# Other.net
KiCad netlist of a schematic drawn in Altium Designer
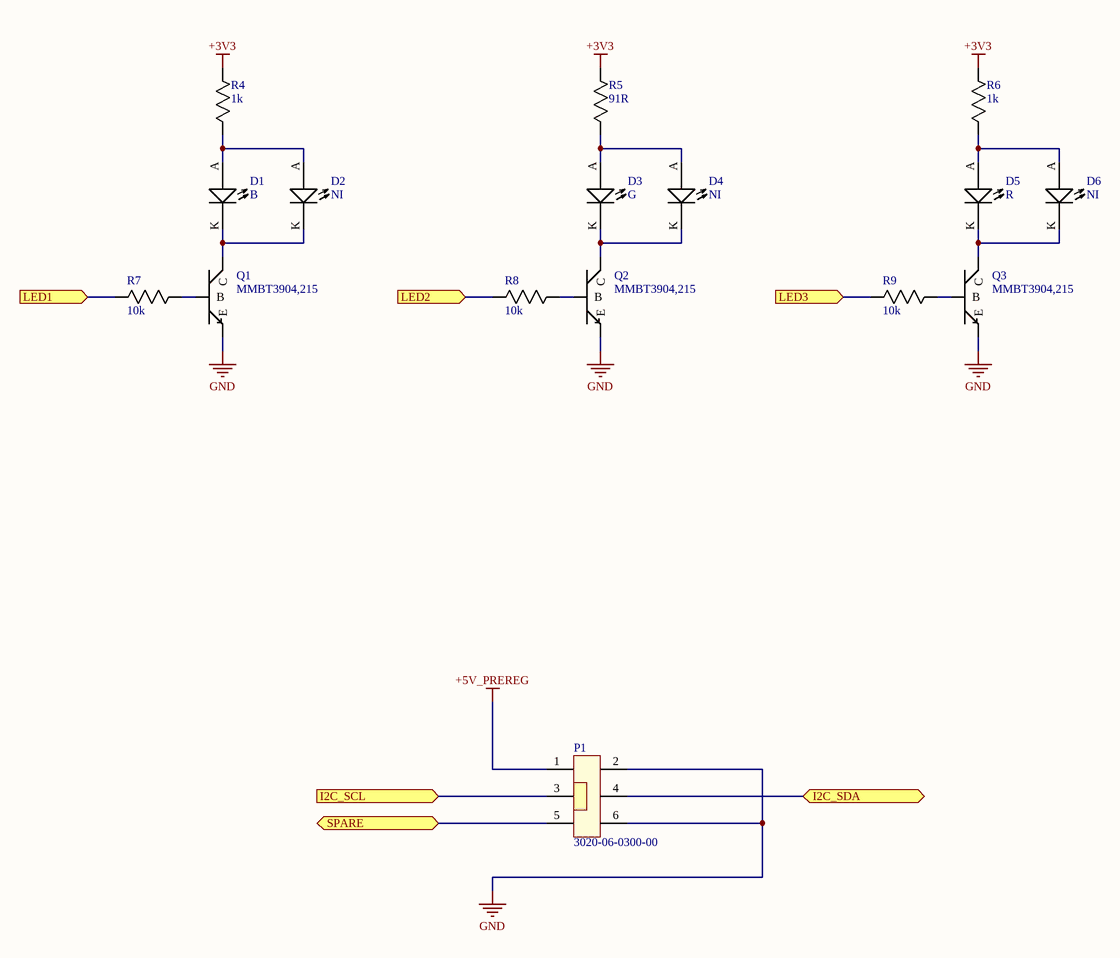
[diagram p0: Other.SchDoc]

(export (version "E")
  (design (tool "Eeschema 10.0.6"))
  (components
    (comp (ref "D1")
      (value "Diode_LED")
      (footprint "0805_LED")
      (description "LED")
      (fields (field (name "MFG") "Wurth") (field (name "TYPE") "B"))
      (libsource (lib "ADAPTONE_CARTE_DE_SON") (part "Diode_LED"))
    )
    (comp (ref "D2")
      (value "Diode_LED")
      (footprint "0805_LED")
      (description "LED")
      (fields (field (name "NI") "NI"))
      (libsource (lib "ADAPTONE_CARTE_DE_SON") (part "Diode_LED"))
    )
    (comp (ref "D3")
      (value "Diode_LED")
      (footprint "0805_LED")
      (description "LED")
      (fields (field (name "MFG") "Osram") (field (name "TYPE") "G"))
      (libsource (lib "ADAPTONE_CARTE_DE_SON") (part "Diode_LED"))
    )
    (comp (ref "D4")
      (value "Diode_LED")
      (footprint "0805_LED")
      (description "LED")
      (fields (field (name "NI") "NI"))
      (libsource (lib "ADAPTONE_CARTE_DE_SON") (part "Diode_LED"))
    )
    (comp (ref "D5")
      (value "Diode_LED")
      (footprint "0805_LED")
      (description "LED")
      (fields (field (name "MFG") "Osram") (field (name "TYPE") "R"))
      (libsource (lib "ADAPTONE_CARTE_DE_SON") (part "Diode_LED"))
    )
    (comp (ref "D6")
      (value "Diode_LED")
      (footprint "0805_LED")
      (description "LED")
      (fields (field (name "NI") "NI"))
      (libsource (lib "ADAPTONE_CARTE_DE_SON") (part "Diode_LED"))
    )
    (comp (ref "P1")
      (value "CON6_3020-06-0300-00")
      (footprint "CONN6_100mils_pol_SMD")
      (description "6-pins")
      (fields (field (name "MFG") "Harwin") (field (name "MFG_PN") "3020-06-0300-00"))
      (libsource (lib "ADAPTONE_CARTE_DE_SON") (part "CON6_3020-06-0300-00"))
    )
    (comp (ref "Q1")
      (value "BJT_N_GDS")
      (footprint "SOT23_GDS")
      (description "BJT NPN")
      (fields (field (name "MFG") "NXP") (field (name "MFG_PN") "MMBT3904,215"))
      (libsource (lib "ADAPTONE_CARTE_DE_SON") (part "BJT_N_GDS"))
    )
    (comp (ref "Q2")
      (value "BJT_N_GDS")
      (footprint "SOT23_GDS")
      (description "BJT NPN")
      (fields (field (name "MFG") "NXP") (field (name "MFG_PN") "MMBT3904,215"))
      (libsource (lib "ADAPTONE_CARTE_DE_SON") (part "BJT_N_GDS"))
    )
    (comp (ref "Q3")
      (value "BJT_N_GDS")
      (footprint "SOT23_GDS")
      (description "BJT NPN")
      (fields (field (name "MFG") "NXP") (field (name "MFG_PN") "MMBT3904,215"))
      (libsource (lib "ADAPTONE_CARTE_DE_SON") (part "BJT_N_GDS"))
    )
    (comp (ref "R4")
      (value "1k")
      (footprint "0603")
      (description "Resistor")
      (fields (field (name "MFG") "Yageo"))
      (libsource (lib "ADAPTONE_CARTE_DE_SON") (part "Resistor"))
    )
    (comp (ref "R5")
      (value "91R")
      (footprint "0603")
      (description "Resistor")
      (fields (field (name "MFG") "Yageo"))
      (libsource (lib "ADAPTONE_CARTE_DE_SON") (part "Resistor"))
    )
    (comp (ref "R6")
      (value "1k")
      (footprint "0603")
      (description "Resistor")
      (fields (field (name "MFG") "Yageo"))
      (libsource (lib "ADAPTONE_CARTE_DE_SON") (part "Resistor"))
    )
    (comp (ref "R7")
      (value "10k")
      (footprint "0603")
      (description "Resistor")
      (fields (field (name "MFG") "Yageo"))
      (libsource (lib "ADAPTONE_CARTE_DE_SON") (part "Resistor"))
    )
    (comp (ref "R8")
      (value "10k")
      (footprint "0603")
      (description "Resistor")
      (fields (field (name "MFG") "Yageo"))
      (libsource (lib "ADAPTONE_CARTE_DE_SON") (part "Resistor"))
    )
    (comp (ref "R9")
      (value "10k")
      (footprint "0603")
      (description "Resistor")
      (fields (field (name "MFG") "Yageo"))
      (libsource (lib "ADAPTONE_CARTE_DE_SON") (part "Resistor"))
    )
  )
  (nets
    (net (code "1") (name "+3V3") (class "Default")
      (node (ref "R4") (pin "2") (pintype "passive"))
      (node (ref "R5") (pin "2") (pintype "passive"))
      (node (ref "R6") (pin "2") (pintype "passive"))
    )
    (net (code "2") (name "+5V_PREREG") (class "Default") (node (ref "P1") (pin "1") (pintype "passive")))
    (net (code "3") (name "/I2C_SCL") (class "Default") (node (ref "P1") (pin "3") (pintype "passive")))
    (net (code "4") (name "/I2C_SDA") (class "Default") (node (ref "P1") (pin "4") (pintype "passive")))
    (net (code "5") (name "/LED1") (class "Default") (node (ref "R7") (pin "1") (pintype "passive")))
    (net (code "6") (name "/LED2") (class "Default") (node (ref "R8") (pin "1") (pintype "passive")))
    (net (code "7") (name "/LED3") (class "Default") (node (ref "R9") (pin "1") (pintype "passive")))
    (net (code "8") (name "/SPARE") (class "Default") (node (ref "P1") (pin "5") (pintype "passive")))
    (net (code "9") (name "GND") (class "Default")
      (node (ref "P1") (pin "2") (pintype "passive"))
      (node (ref "P1") (pin "6") (pintype "passive"))
      (node (ref "Q1") (pin "S") (pinfunction "E_S") (pintype "passive"))
      (node (ref "Q2") (pin "S") (pinfunction "E_S") (pintype "passive"))
      (node (ref "Q3") (pin "S") (pinfunction "E_S") (pintype "passive"))
    )
    (net (code "10") (name "Net-(D1-PadA)") (class "Default")
      (node (ref "D1") (pin "A") (pintype "passive"))
      (node (ref "D2") (pin "A") (pintype "passive"))
      (node (ref "R4") (pin "1") (pintype "passive"))
    )
    (net (code "11") (name "Net-(D3-PadA)") (class "Default")
      (node (ref "D3") (pin "A") (pintype "passive"))
      (node (ref "D4") (pin "A") (pintype "passive"))
      (node (ref "R5") (pin "1") (pintype "passive"))
    )
    (net (code "12") (name "Net-(D5-PadA)") (class "Default")
      (node (ref "D5") (pin "A") (pintype "passive"))
      (node (ref "D6") (pin "A") (pintype "passive"))
      (node (ref "R6") (pin "1") (pintype "passive"))
    )
    (net (code "13") (name "Net-(Q1-B)") (class "Default")
      (node (ref "Q1") (pin "G") (pinfunction "B_G") (pintype "passive"))
      (node (ref "R7") (pin "2") (pintype "passive"))
    )
    (net (code "14") (name "Net-(Q1-C)") (class "Default")
      (node (ref "D1") (pin "K") (pintype "passive"))
      (node (ref "D2") (pin "K") (pintype "passive"))
      (node (ref "Q1") (pin "D") (pinfunction "C_D") (pintype "passive"))
    )
    (net (code "15") (name "Net-(Q2-B)") (class "Default")
      (node (ref "Q2") (pin "G") (pinfunction "B_G") (pintype "passive"))
      (node (ref "R8") (pin "2") (pintype "passive"))
    )
    (net (code "16") (name "Net-(Q2-C)") (class "Default")
      (node (ref "D3") (pin "K") (pintype "passive"))
      (node (ref "D4") (pin "K") (pintype "passive"))
      (node (ref "Q2") (pin "D") (pinfunction "C_D") (pintype "passive"))
    )
    (net (code "17") (name "Net-(Q3-B)") (class "Default")
      (node (ref "Q3") (pin "G") (pinfunction "B_G") (pintype "passive"))
      (node (ref "R9") (pin "2") (pintype "passive"))
    )
    (net (code "18") (name "Net-(Q3-C)") (class "Default")
      (node (ref "D5") (pin "K") (pintype "passive"))
      (node (ref "D6") (pin "K") (pintype "passive"))
      (node (ref "Q3") (pin "D") (pinfunction "C_D") (pintype "passive"))
    )
  )
)
